# untitled.net
KiCad netlist of a schematic drawn in EAGLE
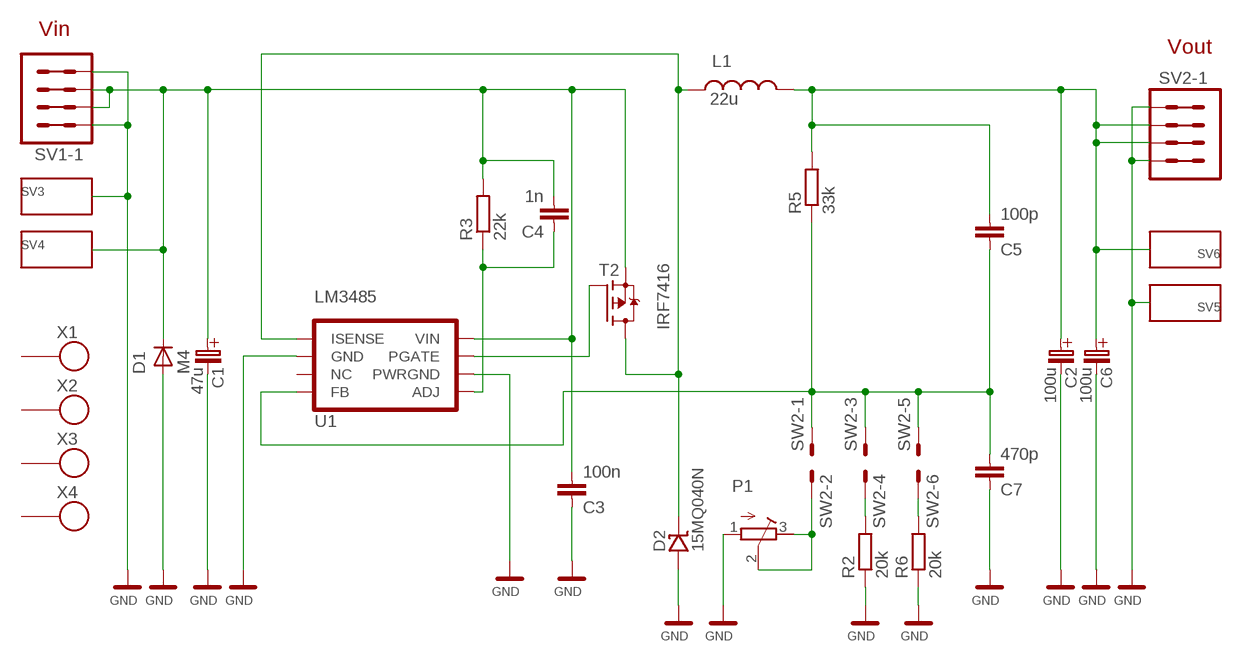
[diagram p0: schematic, sheet 1]

(export (version "E")
  (design (tool "Eeschema 10.0.6"))
  (components
    (comp (ref "C1") (value "47u") (footprint "eagle-import:C") (libsource (lib "eagle-import") (part "C")))
    (comp (ref "C2") (value "100u") (footprint "eagle-import:C") (libsource (lib "eagle-import") (part "C")))
    (comp (ref "C3")
      (value "100n")
      (footprint "eagle-import:C0805")
      (libsource (lib "eagle-import") (part "C0805"))
    )
    (comp (ref "C4")
      (value "1n")
      (footprint "eagle-import:C0805")
      (libsource (lib "eagle-import") (part "C0805"))
    )
    (comp (ref "C5")
      (value "100p")
      (footprint "eagle-import:C0805")
      (libsource (lib "eagle-import") (part "C0805"))
    )
    (comp (ref "C6") (value "100u") (footprint "eagle-import:C") (libsource (lib "eagle-import") (part "C")))
    (comp (ref "C7")
      (value "470p")
      (footprint "eagle-import:C0805")
      (libsource (lib "eagle-import") (part "C0805"))
    )
    (comp (ref "D1")
      (value "M4")
      (footprint "eagle-import:SMA")
      (libsource (lib "eagle-import") (part "D-OB.SMA"))
    )
    (comp (ref "D2")
      (value "15MQ040N")
      (footprint "eagle-import:SMA")
      (libsource (lib "eagle-import") (part "D-SHOTKY-SMA"))
    )
    (comp (ref "L1")
      (value "22u")
      (footprint "eagle-import:DE1205-10")
      (libsource (lib "eagle-import") (part "DE1205-10"))
    )
    (comp (ref "P1")
      (value "TRIM_CA9MTV10")
      (footprint "eagle-import:TRIM_CA9MTV10")
      (libsource (lib "eagle-import") (part "TRIM_CA9MTV10"))
    )
    (comp (ref "R2")
      (value "20k")
      (footprint "eagle-import:0805")
      (libsource (lib "eagle-import") (part "R0805"))
    )
    (comp (ref "R3")
      (value "22k")
      (footprint "eagle-import:0805")
      (libsource (lib "eagle-import") (part "R0805"))
    )
    (comp (ref "R5")
      (value "33k")
      (footprint "eagle-import:0805")
      (libsource (lib "eagle-import") (part "R0805"))
    )
    (comp (ref "R6")
      (value "20k")
      (footprint "eagle-import:0805")
      (libsource (lib "eagle-import") (part "R0805"))
    )
    (comp (ref "SV1")
      (value "MA04-2")
      (footprint "eagle-import:MA04-2")
      (libsource (lib "eagle-import") (part "MA04-2"))
    )
    (comp (ref "SV2")
      (value "MA04-2")
      (footprint "eagle-import:MA04-2")
      (libsource (lib "eagle-import") (part "MA04-2"))
    )
    (comp (ref "SV3")
      (value "WAGO256")
      (footprint "eagle-import:WAGO256")
      (libsource (lib "eagle-import") (part "WAGO256"))
    )
    (comp (ref "SV4")
      (value "WAGO256")
      (footprint "eagle-import:WAGO256")
      (libsource (lib "eagle-import") (part "WAGO256"))
    )
    (comp (ref "SV5")
      (value "WAGO256")
      (footprint "eagle-import:WAGO256")
      (libsource (lib "eagle-import") (part "WAGO256"))
    )
    (comp (ref "SV6")
      (value "WAGO256")
      (footprint "eagle-import:WAGO256")
      (libsource (lib "eagle-import") (part "WAGO256"))
    )
    (comp (ref "SW2")
      (value "MA03-3")
      (footprint "eagle-import:MA03-2")
      (libsource (lib "eagle-import") (part "MA03-3"))
    )
    (comp (ref "T2")
      (value "IRF7416")
      (footprint "eagle-import:SO8")
      (libsource (lib "eagle-import") (part "IRF7416"))
    )
    (comp (ref "U1")
      (value "LM3485")
      (footprint "eagle-import:MSOP-8")
      (libsource (lib "eagle-import") (part "LM3485"))
    )
    (comp (ref "X1")
      (value "SROUB3M")
      (footprint "eagle-import:SROUB3M")
      (libsource (lib "eagle-import") (part "SROUB3M"))
    )
    (comp (ref "X2")
      (value "SROUB3M")
      (footprint "eagle-import:SROUB3M")
      (libsource (lib "eagle-import") (part "SROUB3M"))
    )
    (comp (ref "X3")
      (value "SROUB3M")
      (footprint "eagle-import:SROUB3M")
      (libsource (lib "eagle-import") (part "SROUB3M"))
    )
    (comp (ref "X4")
      (value "SROUB3M")
      (footprint "eagle-import:SROUB3M")
      (libsource (lib "eagle-import") (part "SROUB3M"))
    )
  )
  (nets
    (net (code "1") (name "GND") (class "Default")
      (node (ref "C1") (pin "-") (pinfunction "C_EL-_-") (pintype "passive"))
      (node (ref "C2") (pin "-") (pinfunction "C_EL-_-") (pintype "passive"))
      (node (ref "C3") (pin "1") (pinfunction "1_1") (pintype "passive"))
      (node (ref "C6") (pin "-") (pinfunction "C_EL-_-") (pintype "passive"))
      (node (ref "C7") (pin "1") (pinfunction "1_1") (pintype "passive"))
      (node (ref "D1") (pin "A") (pinfunction "A_A") (pintype "passive"))
      (node (ref "D2") (pin "A") (pinfunction "A_A") (pintype "passive"))
      (node (ref "P1") (pin "1") (pinfunction "1_1") (pintype "passive"))
      (node (ref "R2") (pin "1") (pinfunction "1_1") (pintype "passive"))
      (node (ref "R6") (pin "1") (pinfunction "1_1") (pintype "passive"))
      (node (ref "SV1") (pin "1") (pinfunction "K_1") (pintype "passive"))
      (node (ref "SV1") (pin "2") (pinfunction "K_2") (pintype "passive"))
      (node (ref "SV1") (pin "7") (pinfunction "K_7") (pintype "passive"))
      (node (ref "SV1") (pin "8") (pinfunction "K_8") (pintype "passive"))
      (node (ref "SV2") (pin "1") (pinfunction "K_1") (pintype "passive"))
      (node (ref "SV2") (pin "2") (pinfunction "K_2") (pintype "passive"))
      (node (ref "SV2") (pin "7") (pinfunction "K_7") (pintype "passive"))
      (node (ref "SV2") (pin "8") (pinfunction "K_8") (pintype "passive"))
      (node (ref "SV3") (pin "1") (pinfunction "P$1_1") (pintype "passive"))
      (node (ref "SV3") (pin "A1") (pinfunction "P$1_A1") (pintype "passive"))
      (node (ref "SV5") (pin "1") (pinfunction "P$1_1") (pintype "passive"))
      (node (ref "SV5") (pin "A1") (pinfunction "P$1_A1") (pintype "passive"))
      (node (ref "U1") (pin "2") (pinfunction "GND_2") (pintype "passive"))
      (node (ref "U1") (pin "6") (pinfunction "PWRGND_6") (pintype "passive"))
    )
    (net (code "2") (name "Net-(C1-C_EL+)") (class "Default")
      (node (ref "C1") (pin "+") (pinfunction "C_EL+_+") (pintype "passive"))
      (node (ref "C3") (pin "2") (pinfunction "2_2") (pintype "passive"))
      (node (ref "C4") (pin "2") (pinfunction "2_2") (pintype "passive"))
      (node (ref "D1") (pin "K") (pinfunction "C_K") (pintype "passive"))
      (node (ref "R3") (pin "2") (pinfunction "2_2") (pintype "passive"))
      (node (ref "SV1") (pin "3") (pinfunction "K_3") (pintype "passive"))
      (node (ref "SV1") (pin "4") (pinfunction "K_4") (pintype "passive"))
      (node (ref "SV1") (pin "5") (pinfunction "K_5") (pintype "passive"))
      (node (ref "SV1") (pin "6") (pinfunction "K_6") (pintype "passive"))
      (node (ref "SV4") (pin "1") (pinfunction "P$1_1") (pintype "passive"))
      (node (ref "SV4") (pin "A1") (pinfunction "P$1_A1") (pintype "passive"))
      (node (ref "T2") (pin "1") (pinfunction "S_1") (pintype "passive"))
      (node (ref "T2") (pin "2") (pinfunction "S_2") (pintype "passive"))
      (node (ref "T2") (pin "3") (pinfunction "S_3") (pintype "passive"))
      (node (ref "U1") (pin "8") (pinfunction "VIN_8") (pintype "passive"))
    )
    (net (code "3") (name "Net-(C2-C_EL+)") (class "Default")
      (node (ref "C2") (pin "+") (pinfunction "C_EL+_+") (pintype "passive"))
      (node (ref "C5") (pin "2") (pinfunction "2_2") (pintype "passive"))
      (node (ref "C6") (pin "+") (pinfunction "C_EL+_+") (pintype "passive"))
      (node (ref "L1") (pin "P$2") (pinfunction "2_P$2") (pintype "passive"))
      (node (ref "R5") (pin "2") (pinfunction "2_2") (pintype "passive"))
      (node (ref "SV2") (pin "3") (pinfunction "K_3") (pintype "passive"))
      (node (ref "SV2") (pin "4") (pinfunction "K_4") (pintype "passive"))
      (node (ref "SV2") (pin "5") (pinfunction "K_5") (pintype "passive"))
      (node (ref "SV2") (pin "6") (pinfunction "K_6") (pintype "passive"))
      (node (ref "SV6") (pin "1") (pinfunction "P$1_1") (pintype "passive"))
      (node (ref "SV6") (pin "A1") (pinfunction "P$1_A1") (pintype "passive"))
    )
    (net (code "4") (name "Net-(L1-1)") (class "Default")
      (node (ref "D2") (pin "K") (pinfunction "K_K") (pintype "passive"))
      (node (ref "L1") (pin "P$1") (pinfunction "1_P$1") (pintype "passive"))
      (node (ref "T2") (pin "5") (pinfunction "D_5") (pintype "passive"))
      (node (ref "T2") (pin "6") (pinfunction "D_6") (pintype "passive"))
      (node (ref "T2") (pin "7") (pinfunction "D_7") (pintype "passive"))
      (node (ref "T2") (pin "8") (pinfunction "D_8") (pintype "passive"))
      (node (ref "U1") (pin "1") (pinfunction "ISENSE_1") (pintype "passive"))
    )
    (net (code "5") (name "Net-(SW2A-P$1)") (class "Default")
      (node (ref "C5") (pin "1") (pinfunction "1_1") (pintype "passive"))
      (node (ref "C7") (pin "2") (pinfunction "2_2") (pintype "passive"))
      (node (ref "R5") (pin "1") (pinfunction "1_1") (pintype "passive"))
      (node (ref "SW2") (pin "1") (pinfunction "P$1_1") (pintype "passive"))
      (node (ref "SW2") (pin "3") (pinfunction "P$1_3") (pintype "passive"))
      (node (ref "SW2") (pin "5") (pinfunction "P$1_5") (pintype "passive"))
      (node (ref "U1") (pin "4") (pinfunction "FB_4") (pintype "passive"))
    )
    (net (code "6") (name "Net-(SW2B-P$1)") (class "Default")
      (node (ref "P1") (pin "2") (pinfunction "2_2") (pintype "passive"))
      (node (ref "P1") (pin "3") (pinfunction "3_3") (pintype "passive"))
      (node (ref "SW2") (pin "2") (pinfunction "P$1_2") (pintype "passive"))
    )
    (net (code "7") (name "Net-(SW2D-P$1)") (class "Default")
      (node (ref "R2") (pin "2") (pinfunction "2_2") (pintype "passive"))
      (node (ref "SW2") (pin "4") (pinfunction "P$1_4") (pintype "passive"))
    )
    (net (code "8") (name "Net-(SW2F-P$1)") (class "Default")
      (node (ref "R6") (pin "2") (pinfunction "2_2") (pintype "passive"))
      (node (ref "SW2") (pin "6") (pinfunction "P$1_6") (pintype "passive"))
    )
    (net (code "9") (name "Net-(T2-G)") (class "Default")
      (node (ref "T2") (pin "4") (pinfunction "G_4") (pintype "passive"))
      (node (ref "U1") (pin "7") (pinfunction "PGATE_7") (pintype "passive"))
    )
    (net (code "10") (name "Net-(U1-ADJ)") (class "Default")
      (node (ref "C4") (pin "1") (pinfunction "1_1") (pintype "passive"))
      (node (ref "R3") (pin "1") (pinfunction "1_1") (pintype "passive"))
      (node (ref "U1") (pin "5") (pinfunction "ADJ_5") (pintype "passive"))
    )
    (net (code "11") (name "unconnected-(U1-NC-Pad3)") (class "Default")
      (node (ref "U1") (pin "3") (pinfunction "NC_3") (pintype "passive"))
    )
    (net (code "12") (name "unconnected-(X1-PadP$1)") (class "Default")
      (node (ref "X1") (pin "P$1") (pinfunction "P$1_P$1") (pintype "bidirectional"))
    )
    (net (code "13") (name "unconnected-(X2-PadP$1)") (class "Default")
      (node (ref "X2") (pin "P$1") (pinfunction "P$1_P$1") (pintype "bidirectional"))
    )
    (net (code "14") (name "unconnected-(X3-PadP$1)") (class "Default")
      (node (ref "X3") (pin "P$1") (pinfunction "P$1_P$1") (pintype "bidirectional"))
    )
    (net (code "15") (name "unconnected-(X4-PadP$1)") (class "Default")
      (node (ref "X4") (pin "P$1") (pinfunction "P$1_P$1") (pintype "bidirectional"))
    )
  )
)
